# Audio_Input_Digitial_Mic.net
KiCad netlist of a schematic drawn in Altium Designer
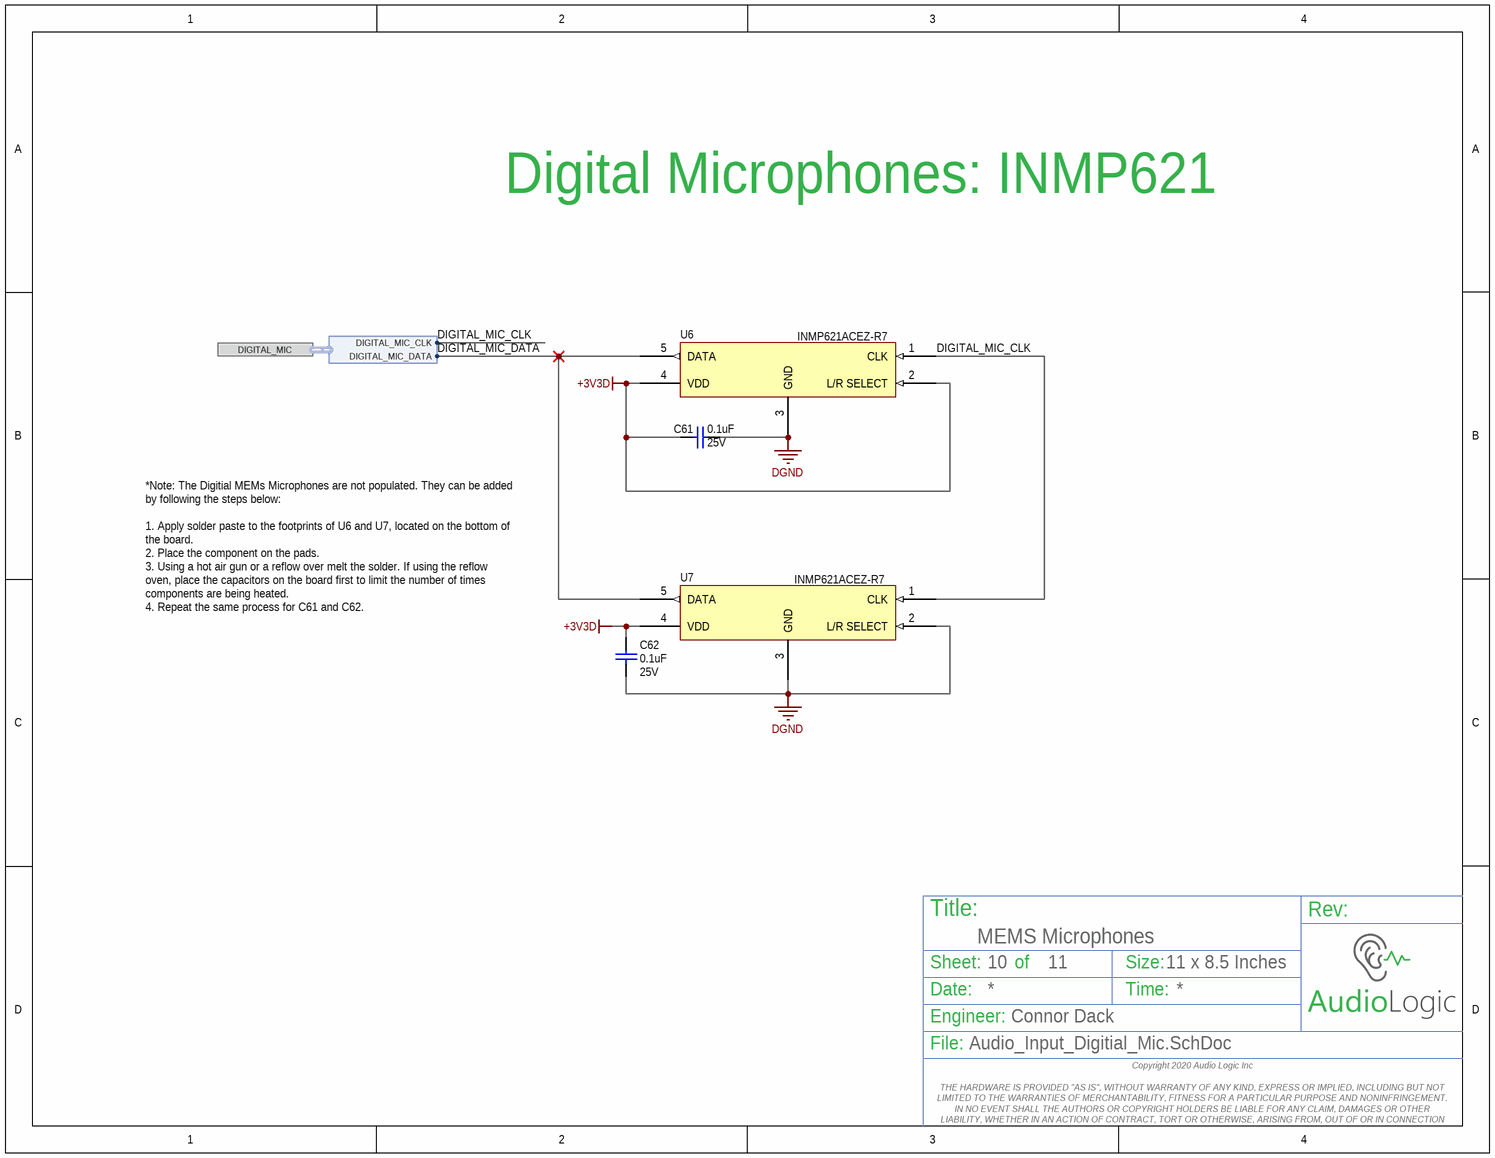
[diagram p0: Audio_Input_Digitial_Mic.SchDoc]

(export (version "E")
  (design (tool "Eeschema 10.0.6"))
  (components
    (comp (ref "C61")
      (value "CGA3E2X7R1E104K080AA")
      (footprint "3-0603_L_DNP")
      (description "CAP CER 0.1UF 25V X7R 0603")
      (fields
        (field (name "MANUFACTURER") "TDK")
        (field (name "TOLERANCE") "10%")
        (field (name "VOLTAGE RATING") "25V")
        (field (name "CAPACITANCE") "0.1uF")
      )
      (libsource (lib "Schematic_Components_CD") (part "CGA3E2X7R1E104K080AA"))
    )
    (comp (ref "C62")
      (value "CGA3E2X7R1E104K080AA")
      (footprint "3-0603_L_DNP")
      (description "CAP CER 0.1UF 25V X7R 0603")
      (fields
        (field (name "MANUFACTURER") "TDK")
        (field (name "TOLERANCE") "10%")
        (field (name "VOLTAGE RATING") "25V")
        (field (name "CAPACITANCE") "0.1uF")
      )
      (libsource (lib "Schematic_Components_CD") (part "CGA3E2X7R1E104K080AA"))
    )
    (comp (ref "U6")
      (value "INMP621")
      (footprint "INMP621_DNP")
      (fields
        (field (name "MANUFACTURER") "InvenSense")
        (field (name "MANUFACTURER PART NUMBER") "INMP621ACEZ-R7")
      )
      (libsource (lib "Schematic_Components_CD") (part "INMP621"))
    )
    (comp (ref "U7")
      (value "INMP621")
      (footprint "INMP621_DNP")
      (fields
        (field (name "MANUFACTURER") "InvenSense")
        (field (name "MANUFACTURER PART NUMBER") "INMP621ACEZ-R7")
      )
      (libsource (lib "Schematic_Components_CD") (part "INMP621"))
    )
  )
  (nets
    (net (code "2") (name "+3V3D") (class "Default")
      (node (ref "C61") (pin "2") (pinfunction "2_2") (pintype "passive"))
      (node (ref "C62") (pin "1") (pinfunction "1_1") (pintype "passive"))
      (node (ref "U6") (pin "2") (pinfunction "L/R_SELECT_2") (pintype "input"))
      (node (ref "U6") (pin "4") (pinfunction "VDD_4") (pintype "passive"))
      (node (ref "U7") (pin "4") (pinfunction "VDD_4") (pintype "passive"))
    )
    (net (code "3") (name "/DIGITAL_MIC_CLK") (class "Default")
      (node (ref "U6") (pin "1") (pinfunction "CLK_1") (pintype "input"))
      (node (ref "U7") (pin "1") (pinfunction "CLK_1") (pintype "input"))
    )
    (net (code "4") (name "/DIGITAL_MIC_DATA") (class "Default")
      (node (ref "U6") (pin "5") (pinfunction "DATA_5") (pintype "output"))
      (node (ref "U7") (pin "5") (pinfunction "DATA_5") (pintype "output"))
    )
    (net (code "6") (name "DGND") (class "Default")
      (node (ref "C61") (pin "1") (pinfunction "1_1") (pintype "passive"))
      (node (ref "C62") (pin "2") (pinfunction "2_2") (pintype "passive"))
      (node (ref "U6") (pin "3") (pinfunction "GND_3") (pintype "passive"))
      (node (ref "U7") (pin "2") (pinfunction "L/R_SELECT_2") (pintype "input"))
      (node (ref "U7") (pin "3") (pinfunction "GND_3") (pintype "passive"))
    )
  )
)
